# CH340T_to_TTL.net
KiCad netlist of a schematic drawn in Altium Designer
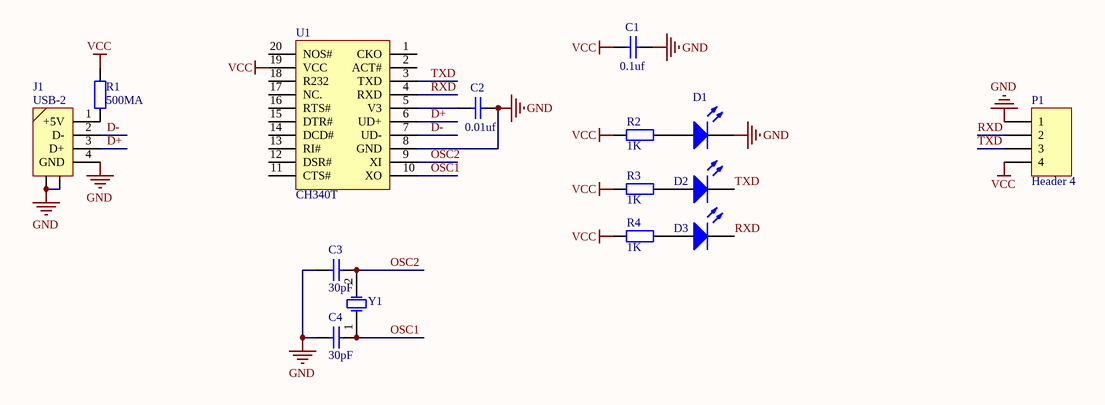
[diagram p0: CH340T to TTL.SchDoc]

(export (version "E")
  (design (tool "Eeschema 10.0.6"))
  (components
    (comp (ref "C1")
      (value "0.1uf")
      (footprint "0805S")
      (description "Capacitor")
      (fields (field (name "Comment") "Cap") (field (name "PUBLISHER") "Altium Limited"))
      (libsource (lib "myintlib") (part "Cap"))
    )
    (comp (ref "C2")
      (value "0.01uf")
      (footprint "0805S")
      (description "Capacitor")
      (fields (field (name "Comment") "Cap") (field (name "PUBLISHER") "Altium Limited"))
      (libsource (lib "myintlib") (part "Cap"))
    )
    (comp (ref "C3")
      (value "30pF")
      (footprint "0805S")
      (description "Capacitor")
      (fields (field (name "Comment") "Cap") (field (name "PUBLISHER") "Altium Limited"))
      (libsource (lib "Miscellaneous Devices") (part "Cap"))
    )
    (comp (ref "C4")
      (value "30pF")
      (footprint "0805S")
      (description "Capacitor")
      (fields (field (name "Comment") "Cap") (field (name "PUBLISHER") "Altium Limited"))
      (libsource (lib "Miscellaneous Devices") (part "Cap"))
    )
    (comp (ref "D1")
      (value "LED")
      (footprint "LED0805")
      (description "Typical INFRARED GaAs LED")
      (fields (field (name "PUBLISHER") "Altium Limited"))
      (libsource (lib "myintlib") (part "LED0"))
    )
    (comp (ref "D2")
      (value "LED")
      (footprint "LED0805")
      (description "Typical INFRARED GaAs LED")
      (fields (field (name "PUBLISHER") "Altium Limited"))
      (libsource (lib "myintlib") (part "LED0"))
    )
    (comp (ref "D3")
      (value "LED")
      (footprint "LED0805")
      (description "Typical INFRARED GaAs LED")
      (fields (field (name "PUBLISHER") "Altium Limited"))
      (libsource (lib "myintlib") (part "LED0"))
    )
    (comp (ref "J1") (value "USB-2") (footprint "USB-SM-A") (libsource (lib "myintlib") (part "USB-2")))
    (comp (ref "P1")
      (value "Header 4")
      (footprint "HDR1X4")
      (description "Header, 4-Pin")
      (fields (field (name "PUBLISHER") "Altium Limited"))
      (libsource (lib "Connectors") (part "Header 4"))
    )
    (comp (ref "R1")
      (value "500MA")
      (footprint "0805S")
      (description "Resistor")
      (fields (field (name "Comment") "Res2") (field (name "PUBLISHER") "Altium Limited"))
      (libsource (lib "") (part "Res2_1"))
    )
    (comp (ref "R2")
      (value "1K")
      (footprint "0805S")
      (description "Resistor")
      (fields (field (name "Comment") "Res2") (field (name "PUBLISHER") "Altium Limited"))
      (libsource (lib "myintlib") (part "Res2"))
    )
    (comp (ref "R3")
      (value "1K")
      (footprint "0805S")
      (description "Resistor")
      (fields (field (name "Comment") "Res2") (field (name "PUBLISHER") "Altium Limited"))
      (libsource (lib "myintlib") (part "Res2"))
    )
    (comp (ref "R4")
      (value "1K")
      (footprint "0805S")
      (description "Resistor")
      (fields (field (name "Comment") "Res2") (field (name "PUBLISHER") "Altium Limited"))
      (libsource (lib "myintlib") (part "Res2"))
    )
    (comp (ref "U1") (value "CH340T") (footprint "SSOP20") (libsource (lib "myintlib") (part "CH340T")))
    (comp (ref "Y1")
      (value "XTAL")
      (footprint "XTAL-T3")
      (description "Crystal Oscillator")
      (fields (field (name "PUBLISHER") "Altium Limited"))
      (libsource (lib "Miscellaneous Devices") (part "XTAL"))
    )
  )
  (nets
    (net (code "1") (name "/D+") (class "Default")
      (node (ref "J1") (pin "3") (pinfunction "D+_3") (pintype "passive"))
      (node (ref "U1") (pin "6") (pinfunction "UD+_6") (pintype "passive"))
    )
    (net (code "2") (name "/D-") (class "Default")
      (node (ref "J1") (pin "2") (pinfunction "D-_2") (pintype "passive"))
      (node (ref "U1") (pin "7") (pinfunction "UD-_7") (pintype "passive"))
    )
    (net (code "3") (name "/OSC1") (class "Default")
      (node (ref "C4") (pin "1") (pinfunction "1_1") (pintype "passive"))
      (node (ref "U1") (pin "10") (pinfunction "XO_10") (pintype "passive"))
      (node (ref "Y1") (pin "1") (pinfunction "OSC1_1") (pintype "passive"))
    )
    (net (code "4") (name "/OSC2") (class "Default")
      (node (ref "C3") (pin "1") (pinfunction "1_1") (pintype "passive"))
      (node (ref "U1") (pin "9") (pinfunction "XI_9") (pintype "passive"))
      (node (ref "Y1") (pin "2") (pinfunction "OSC2_2") (pintype "passive"))
    )
    (net (code "5") (name "/RXD") (class "Default")
      (node (ref "D3") (pin "2") (pinfunction "2_2") (pintype "passive"))
      (node (ref "P1") (pin "2") (pinfunction "2_2") (pintype "passive"))
      (node (ref "U1") (pin "4") (pinfunction "RXD_4") (pintype "passive"))
    )
    (net (code "6") (name "/TXD") (class "Default")
      (node (ref "D2") (pin "2") (pinfunction "2_2") (pintype "passive"))
      (node (ref "P1") (pin "3") (pinfunction "3_3") (pintype "passive"))
      (node (ref "U1") (pin "3") (pinfunction "TXD_3") (pintype "passive"))
    )
    (net (code "7") (name "GND") (class "Default")
      (node (ref "C1") (pin "1") (pinfunction "1_1") (pintype "passive"))
      (node (ref "C2") (pin "1") (pinfunction "1_1") (pintype "passive"))
      (node (ref "C3") (pin "2") (pinfunction "2_2") (pintype "passive"))
      (node (ref "C4") (pin "2") (pinfunction "2_2") (pintype "passive"))
      (node (ref "D1") (pin "2") (pinfunction "2_2") (pintype "passive"))
      (node (ref "J1") (pin "4") (pinfunction "GND_4") (pintype "passive"))
      (node (ref "J1") (pin "5") (pinfunction "5_5") (pintype "passive"))
      (node (ref "J1") (pin "6") (pinfunction "6_6") (pintype "passive"))
      (node (ref "P1") (pin "1") (pinfunction "1_1") (pintype "passive"))
      (node (ref "U1") (pin "8") (pinfunction "GND_8") (pintype "passive"))
    )
    (net (code "8") (name "Net-(D1-Pad1)") (class "Default")
      (node (ref "D1") (pin "1") (pinfunction "1_1") (pintype "passive"))
      (node (ref "R2") (pin "2") (pinfunction "2_2") (pintype "passive"))
    )
    (net (code "9") (name "Net-(D2-Pad1)") (class "Default")
      (node (ref "D2") (pin "1") (pinfunction "1_1") (pintype "passive"))
      (node (ref "R3") (pin "2") (pinfunction "2_2") (pintype "passive"))
    )
    (net (code "10") (name "Net-(D3-Pad1)") (class "Default")
      (node (ref "D3") (pin "1") (pinfunction "1_1") (pintype "passive"))
      (node (ref "R4") (pin "2") (pinfunction "2_2") (pintype "passive"))
    )
    (net (code "11") (name "Net-(J1-+5V)") (class "Default")
      (node (ref "J1") (pin "1") (pinfunction "+5V_1") (pintype "passive"))
      (node (ref "R1") (pin "1") (pinfunction "1_1") (pintype "passive"))
    )
    (net (code "12") (name "Net-(U1-V3)") (class "Default")
      (node (ref "C2") (pin "2") (pinfunction "2_2") (pintype "passive"))
      (node (ref "U1") (pin "5") (pinfunction "V3_5") (pintype "passive"))
    )
    (net (code "13") (name "VCC") (class "Default")
      (node (ref "C1") (pin "2") (pinfunction "2_2") (pintype "passive"))
      (node (ref "P1") (pin "4") (pinfunction "4_4") (pintype "passive"))
      (node (ref "R1") (pin "2") (pinfunction "2_2") (pintype "passive"))
      (node (ref "R2") (pin "1") (pinfunction "1_1") (pintype "passive"))
      (node (ref "R3") (pin "1") (pinfunction "1_1") (pintype "passive"))
      (node (ref "R4") (pin "1") (pinfunction "1_1") (pintype "passive"))
      (node (ref "U1") (pin "19") (pinfunction "VCC_19") (pintype "passive"))
    )
    (net (code "14") (name "unconnected-(U1-ACT#-Pad2)") (class "Default")
      (node (ref "U1") (pin "2") (pinfunction "ACT#_2") (pintype "passive"))
    )
    (net (code "15") (name "unconnected-(U1-CKO-Pad1)") (class "Default")
      (node (ref "U1") (pin "1") (pinfunction "CKO_1") (pintype "passive"))
    )
    (net (code "16") (name "unconnected-(U1-CTS#-Pad11)") (class "Default")
      (node (ref "U1") (pin "11") (pinfunction "CTS#_11") (pintype "passive"))
    )
    (net (code "17") (name "unconnected-(U1-DCD#-Pad14)") (class "Default")
      (node (ref "U1") (pin "14") (pinfunction "DCD#_14") (pintype "passive"))
    )
    (net (code "18") (name "unconnected-(U1-DSR#-Pad12)") (class "Default")
      (node (ref "U1") (pin "12") (pinfunction "DSR#_12") (pintype "passive"))
    )
    (net (code "19") (name "unconnected-(U1-DTR#-Pad15)") (class "Default")
      (node (ref "U1") (pin "15") (pinfunction "DTR#_15") (pintype "passive"))
    )
    (net (code "20") (name "unconnected-(U1-NC.-Pad17)") (class "Default")
      (node (ref "U1") (pin "17") (pinfunction "NC._17") (pintype "passive"))
    )
    (net (code "21") (name "unconnected-(U1-NOS#-Pad20)") (class "Default")
      (node (ref "U1") (pin "20") (pinfunction "NOS#_20") (pintype "passive"))
    )
    (net (code "22") (name "unconnected-(U1-R232-Pad18)") (class "Default")
      (node (ref "U1") (pin "18") (pinfunction "R232_18") (pintype "passive"))
    )
    (net (code "23") (name "unconnected-(U1-RI#-Pad13)") (class "Default")
      (node (ref "U1") (pin "13") (pinfunction "RI#_13") (pintype "passive"))
    )
    (net (code "24") (name "unconnected-(U1-RTS#-Pad16)") (class "Default")
      (node (ref "U1") (pin "16") (pinfunction "RTS#_16") (pintype "passive"))
    )
  )
)
